# tinker.net
KiCad netlist of a schematic drawn in EAGLE
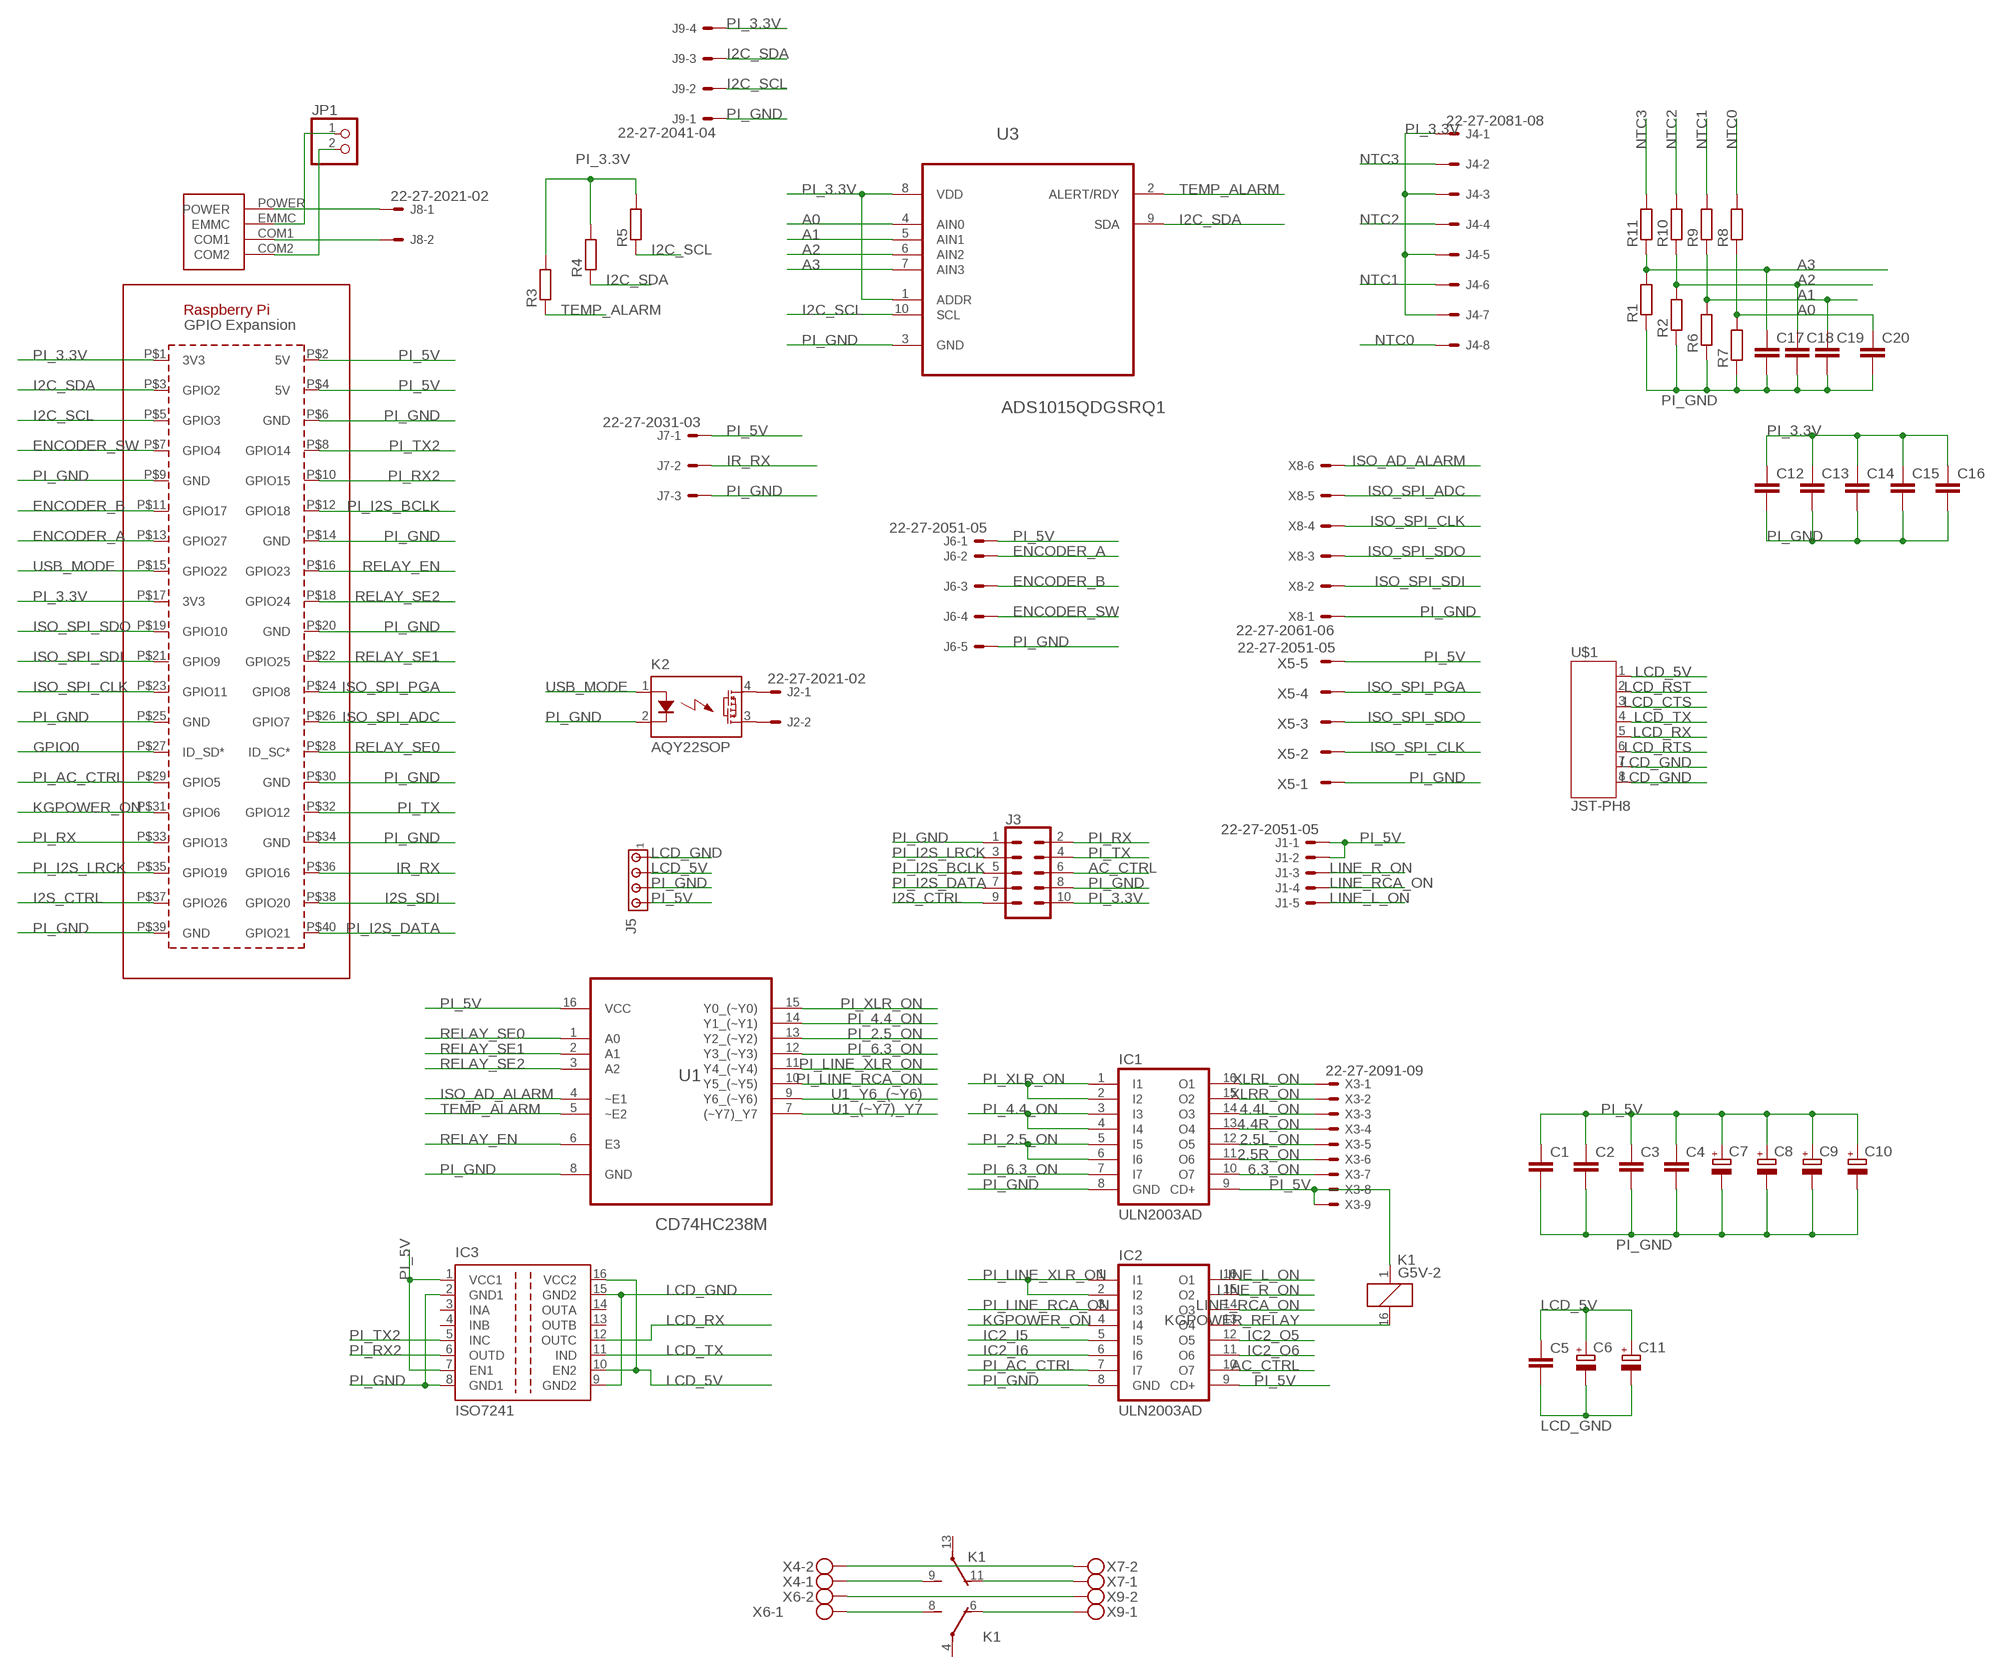
[diagram p0: schematic, sheet 1]

(export (version "E")
  (design (tool "Eeschema 10.0.6"))
  (components
    (comp (ref "C1")
      (value "C-EUC0603")
      (footprint "eagle-import:C0603")
      (libsource (lib "eagle-import") (part "C-EUC0603"))
    )
    (comp (ref "C2")
      (value "C-EUC0603")
      (footprint "eagle-import:C0603")
      (libsource (lib "eagle-import") (part "C-EUC0603"))
    )
    (comp (ref "C3")
      (value "C-EUC0603")
      (footprint "eagle-import:C0603")
      (libsource (lib "eagle-import") (part "C-EUC0603"))
    )
    (comp (ref "C4")
      (value "C-EUC0603")
      (footprint "eagle-import:C0603")
      (libsource (lib "eagle-import") (part "C-EUC0603"))
    )
    (comp (ref "C5")
      (value "C-EUC0603")
      (footprint "eagle-import:C0603")
      (libsource (lib "eagle-import") (part "C-EUC0603"))
    )
    (comp (ref "C6")
      (value "CPOL-EUSP-CAP-CX")
      (footprint "eagle-import:SP-CAP-CX")
      (libsource (lib "eagle-import") (part "CPOL-EUSP-CAP-CX"))
    )
    (comp (ref "C7")
      (value "CPOL-EUE5-10.5")
      (footprint "eagle-import:E5-10,5")
      (libsource (lib "eagle-import") (part "CPOL-EUE5-10.5"))
    )
    (comp (ref "C8")
      (value "CPOL-EUE5-10.5")
      (footprint "eagle-import:E5-10,5")
      (libsource (lib "eagle-import") (part "CPOL-EUE5-10.5"))
    )
    (comp (ref "C9")
      (value "CPOL-EUE5-10.5")
      (footprint "eagle-import:E5-10,5")
      (libsource (lib "eagle-import") (part "CPOL-EUE5-10.5"))
    )
    (comp (ref "C10")
      (value "CPOL-EUE5-10.5")
      (footprint "eagle-import:E5-10,5")
      (libsource (lib "eagle-import") (part "CPOL-EUE5-10.5"))
    )
    (comp (ref "C11")
      (value "CPOL-EUSP-CAP-CX")
      (footprint "eagle-import:SP-CAP-CX")
      (libsource (lib "eagle-import") (part "CPOL-EUSP-CAP-CX"))
    )
    (comp (ref "C12")
      (value "C-EUC0603")
      (footprint "eagle-import:C0603")
      (libsource (lib "eagle-import") (part "C-EUC0603"))
    )
    (comp (ref "C13")
      (value "C-EUC0603")
      (footprint "eagle-import:C0603")
      (libsource (lib "eagle-import") (part "C-EUC0603"))
    )
    (comp (ref "C14")
      (value "C-EUC0603")
      (footprint "eagle-import:C0603")
      (libsource (lib "eagle-import") (part "C-EUC0603"))
    )
    (comp (ref "C15")
      (value "C-EUC0603")
      (footprint "eagle-import:C0603")
      (libsource (lib "eagle-import") (part "C-EUC0603"))
    )
    (comp (ref "C16")
      (value "C-EUC0603")
      (footprint "eagle-import:C0603")
      (libsource (lib "eagle-import") (part "C-EUC0603"))
    )
    (comp (ref "C17")
      (value "C-EUC0603")
      (footprint "eagle-import:C0603")
      (libsource (lib "eagle-import") (part "C-EUC0603"))
    )
    (comp (ref "C18")
      (value "C-EUC0603")
      (footprint "eagle-import:C0603")
      (libsource (lib "eagle-import") (part "C-EUC0603"))
    )
    (comp (ref "C19")
      (value "C-EUC0603")
      (footprint "eagle-import:C0603")
      (libsource (lib "eagle-import") (part "C-EUC0603"))
    )
    (comp (ref "C20")
      (value "C-EUC0603")
      (footprint "eagle-import:C0603")
      (libsource (lib "eagle-import") (part "C-EUC0603"))
    )
    (comp (ref "IC1")
      (value "ULN2003AD")
      (footprint "eagle-import:SO16")
      (libsource (lib "eagle-import") (part "ULN2003AD"))
    )
    (comp (ref "IC2")
      (value "ULN2003AD")
      (footprint "eagle-import:SO16")
      (libsource (lib "eagle-import") (part "ULN2003AD"))
    )
    (comp (ref "IC3")
      (value "ISO7241")
      (footprint "eagle-import:SO-16DW")
      (fields (field (name "MPN") "ISO7241CDW"))
      (libsource (lib "eagle-import") (part "ISO7241"))
    )
    (comp (ref "J1")
      (value "22-27-2051-05")
      (footprint "eagle-import:6410-05")
      (fields (field (name "MF") "MOLEX"))
      (libsource (lib "eagle-import") (part "22-?-0527-2051"))
    )
    (comp (ref "J2")
      (value "22-27-2021-02")
      (footprint "eagle-import:6410-02")
      (fields (field (name "MF") "MOLEX"))
      (libsource (lib "eagle-import") (part "22-?-0227-2021"))
    )
    (comp (ref "J3")
      (value "CONN_05X2SHD_LOCK")
      (footprint "eagle-import:2X5-SHROUDED_LOCK")
      (libsource (lib "eagle-import") (part "CONN_05X2SHD_LOCK"))
    )
    (comp (ref "J4")
      (value "22-27-2081-08")
      (footprint "eagle-import:6410-08")
      (fields (field (name "MF") "MOLEX"))
      (libsource (lib "eagle-import") (part "22-?-0827-2081"))
    )
    (comp (ref "J5")
      (value "MTA04-156")
      (footprint "eagle-import:1X4MTA")
      (libsource (lib "eagle-import") (part "MTA04-156"))
    )
    (comp (ref "J6")
      (value "22-27-2051-05")
      (footprint "eagle-import:6410-05")
      (fields (field (name "MF") "MOLEX"))
      (libsource (lib "eagle-import") (part "22-?-0527-2051"))
    )
    (comp (ref "J7")
      (value "22-27-2031-03")
      (footprint "eagle-import:6410-03")
      (fields (field (name "MF") "MOLEX"))
      (libsource (lib "eagle-import") (part "22-?-0327-2031"))
    )
    (comp (ref "J8")
      (value "22-27-2021-02")
      (footprint "eagle-import:6410-02")
      (fields (field (name "MF") "MOLEX"))
      (libsource (lib "eagle-import") (part "22-?-0227-2021"))
    )
    (comp (ref "J9")
      (value "22-27-2041-04")
      (footprint "eagle-import:6410-04")
      (fields (field (name "MF") "MOLEX"))
      (libsource (lib "eagle-import") (part "22-?-0427-2041"))
    )
    (comp (ref "JP1")
      (value "PINHD-1X2")
      (footprint "eagle-import:1X02")
      (libsource (lib "eagle-import") (part "PINHD-1X2"))
    )
    (comp (ref "K1")
      (value "G5V-2")
      (footprint "eagle-import:G5V-2")
      (fields (field (name "MPN") "G5V-2 5DC"))
      (libsource (lib "eagle-import") (part "G5V-2"))
    )
    (comp (ref "K2")
      (value "AQY22SOP")
      (footprint "eagle-import:SOP04")
      (libsource (lib "eagle-import") (part "AQYSOP22"))
    )
    (comp (ref "PCB1")
      (value "RPI3")
      (footprint "eagle-import:RPI3")
      (libsource (lib "eagle-import") (part "RPI3"))
    )
    (comp (ref "R1")
      (value "R-EU_MELF0204W")
      (footprint "eagle-import:MINI_MELF-0204W")
      (libsource (lib "eagle-import") (part "R-EU_MELF0204W"))
    )
    (comp (ref "R2")
      (value "R-EU_MELF0204W")
      (footprint "eagle-import:MINI_MELF-0204W")
      (libsource (lib "eagle-import") (part "R-EU_MELF0204W"))
    )
    (comp (ref "R3")
      (value "R-EU_MELF0204W")
      (footprint "eagle-import:MINI_MELF-0204W")
      (libsource (lib "eagle-import") (part "R-EU_MELF0204W"))
    )
    (comp (ref "R4")
      (value "R-EU_MELF0204W")
      (footprint "eagle-import:MINI_MELF-0204W")
      (libsource (lib "eagle-import") (part "R-EU_MELF0204W"))
    )
    (comp (ref "R5")
      (value "R-EU_MELF0204W")
      (footprint "eagle-import:MINI_MELF-0204W")
      (libsource (lib "eagle-import") (part "R-EU_MELF0204W"))
    )
    (comp (ref "R6")
      (value "R-EU_MELF0204W")
      (footprint "eagle-import:MINI_MELF-0204W")
      (libsource (lib "eagle-import") (part "R-EU_MELF0204W"))
    )
    (comp (ref "R7")
      (value "R-EU_MELF0204W")
      (footprint "eagle-import:MINI_MELF-0204W")
      (libsource (lib "eagle-import") (part "R-EU_MELF0204W"))
    )
    (comp (ref "R8")
      (value "R-EU_MELF0204W")
      (footprint "eagle-import:MINI_MELF-0204W")
      (libsource (lib "eagle-import") (part "R-EU_MELF0204W"))
    )
    (comp (ref "R9")
      (value "R-EU_MELF0204W")
      (footprint "eagle-import:MINI_MELF-0204W")
      (libsource (lib "eagle-import") (part "R-EU_MELF0204W"))
    )
    (comp (ref "R10")
      (value "R-EU_MELF0204W")
      (footprint "eagle-import:MINI_MELF-0204W")
      (libsource (lib "eagle-import") (part "R-EU_MELF0204W"))
    )
    (comp (ref "R11")
      (value "R-EU_MELF0204W")
      (footprint "eagle-import:MINI_MELF-0204W")
      (libsource (lib "eagle-import") (part "R-EU_MELF0204W"))
    )
    (comp (ref "U$1")
      (value "JST-PH8")
      (footprint "eagle-import:JST-PH8")
      (libsource (lib "eagle-import") (part "JST-PH8"))
    )
    (comp (ref "U1")
      (value "CD74HC238M")
      (footprint "eagle-import:SOIC127P600X175-16N")
      (libsource (lib "eagle-import") (part "CD74HC238M"))
    )
    (comp (ref "U3")
      (value "ADS1015QDGSRQ1")
      (footprint "eagle-import:SOP50P490X110-10N")
      (libsource (lib "eagle-import") (part "ADS1015QDGSRQ1"))
    )
    (comp (ref "X3")
      (value "22-27-2091-09")
      (footprint "eagle-import:6410-09")
      (fields (field (name "MF") "MOLEX"))
      (libsource (lib "eagle-import") (part "22-?-0927-2091"))
    )
    (comp (ref "X4")
      (value "CON-PHOENIX-508_MKDSN1,5/2-5,08")
      (footprint "eagle-import:CON-PHOENIX-508_MKDSN1,5_2-5,08")
      (libsource (lib "eagle-import") (part "CON-PHOENIX-508_MKDSN1,5/2-5,08"))
    )
    (comp (ref "X5")
      (value "22-27-2051-05")
      (footprint "eagle-import:6410-05")
      (fields (field (name "MF") "MOLEX"))
      (libsource (lib "eagle-import") (part "22-?-0527-2051"))
    )
    (comp (ref "X6")
      (value "CON-PHOENIX-508_MKDSN1,5/2-5,08")
      (footprint "eagle-import:CON-PHOENIX-508_MKDSN1,5_2-5,08")
      (libsource (lib "eagle-import") (part "CON-PHOENIX-508_MKDSN1,5/2-5,08"))
    )
    (comp (ref "X7")
      (value "CON-PHOENIX-508_MKDSN1,5/2-5,08")
      (footprint "eagle-import:CON-PHOENIX-508_MKDSN1,5_2-5,08")
      (libsource (lib "eagle-import") (part "CON-PHOENIX-508_MKDSN1,5/2-5,08"))
    )
    (comp (ref "X8")
      (value "22-27-2061-06")
      (footprint "eagle-import:6410-06")
      (fields (field (name "MF") "MOLEX"))
      (libsource (lib "eagle-import") (part "22-?-0627-2061"))
    )
    (comp (ref "X9")
      (value "CON-PHOENIX-508_MKDSN1,5/2-5,08")
      (footprint "eagle-import:CON-PHOENIX-508_MKDSN1,5_2-5,08")
      (libsource (lib "eagle-import") (part "CON-PHOENIX-508_MKDSN1,5/2-5,08"))
    )
  )
  (nets
    (net (code "1") (name "/2.5L_ON") (class "Default")
      (node (ref "IC1") (pin "12") (pinfunction "O5_12") (pintype "open_collector"))
      (node (ref "X3") (pin "5") (pinfunction "S_5") (pintype "passive"))
    )
    (net (code "2") (name "/2.5R_ON") (class "Default")
      (node (ref "IC1") (pin "11") (pinfunction "O6_11") (pintype "open_collector"))
      (node (ref "X3") (pin "6") (pinfunction "S_6") (pintype "passive"))
    )
    (net (code "3") (name "/4.4L_ON") (class "Default")
      (node (ref "IC1") (pin "14") (pinfunction "O3_14") (pintype "open_collector"))
      (node (ref "X3") (pin "3") (pinfunction "S_3") (pintype "passive"))
    )
    (net (code "4") (name "/4.4R_ON") (class "Default")
      (node (ref "IC1") (pin "13") (pinfunction "O4_13") (pintype "open_collector"))
      (node (ref "X3") (pin "4") (pinfunction "S_4") (pintype "passive"))
    )
    (net (code "5") (name "/6.3_ON") (class "Default")
      (node (ref "IC1") (pin "10") (pinfunction "O7_10") (pintype "open_collector"))
      (node (ref "X3") (pin "7") (pinfunction "S_7") (pintype "passive"))
    )
    (net (code "6") (name "/A0") (class "Default")
      (node (ref "C20") (pin "1") (pinfunction "1_1") (pintype "passive"))
      (node (ref "R7") (pin "2") (pinfunction "2_2") (pintype "passive"))
      (node (ref "R8") (pin "1") (pinfunction "1_1") (pintype "passive"))
      (node (ref "U3") (pin "4") (pinfunction "AIN0_4") (pintype "input"))
    )
    (net (code "7") (name "/A1") (class "Default")
      (node (ref "C19") (pin "1") (pinfunction "1_1") (pintype "passive"))
      (node (ref "R6") (pin "2") (pinfunction "2_2") (pintype "passive"))
      (node (ref "R9") (pin "1") (pinfunction "1_1") (pintype "passive"))
      (node (ref "U3") (pin "5") (pinfunction "AIN1_5") (pintype "input"))
    )
    (net (code "8") (name "/A2") (class "Default")
      (node (ref "C18") (pin "1") (pinfunction "1_1") (pintype "passive"))
      (node (ref "R10") (pin "1") (pinfunction "1_1") (pintype "passive"))
      (node (ref "R2") (pin "2") (pinfunction "2_2") (pintype "passive"))
      (node (ref "U3") (pin "6") (pinfunction "AIN2_6") (pintype "input"))
    )
    (net (code "9") (name "/A3") (class "Default")
      (node (ref "C17") (pin "1") (pinfunction "1_1") (pintype "passive"))
      (node (ref "R1") (pin "2") (pinfunction "2_2") (pintype "passive"))
      (node (ref "R11") (pin "1") (pinfunction "1_1") (pintype "passive"))
      (node (ref "U3") (pin "7") (pinfunction "AIN3_7") (pintype "input"))
    )
    (net (code "10") (name "/AC_CTRL") (class "Default")
      (node (ref "IC2") (pin "10") (pinfunction "O7_10") (pintype "open_collector"))
      (node (ref "J3") (pin "6") (pinfunction "6_6") (pintype "passive"))
    )
    (net (code "11") (name "/ENCODER_A") (class "Default")
      (node (ref "J6") (pin "2") (pinfunction "S_2") (pintype "passive"))
      (node (ref "PCB1") (pin "P$13") (pinfunction "GPIO27_P$13") (pintype "bidirectional"))
    )
    (net (code "12") (name "/ENCODER_B") (class "Default")
      (node (ref "J6") (pin "3") (pinfunction "S_3") (pintype "passive"))
      (node (ref "PCB1") (pin "P$11") (pinfunction "GPIO17_P$11") (pintype "bidirectional"))
    )
    (net (code "13") (name "/ENCODER_SW") (class "Default")
      (node (ref "J6") (pin "4") (pinfunction "S_4") (pintype "passive"))
      (node (ref "PCB1") (pin "P$7") (pinfunction "GPIO4_P$7") (pintype "bidirectional"))
    )
    (net (code "14") (name "/GPIO0") (class "Default")
      (node (ref "PCB1") (pin "P$27") (pinfunction "ID_SD*_P$27") (pintype "bidirectional"))
    )
    (net (code "15") (name "/I2C_SCL") (class "Default")
      (node (ref "J9") (pin "2") (pinfunction "S_2") (pintype "passive"))
      (node (ref "PCB1") (pin "P$5") (pinfunction "GPIO3_P$5") (pintype "bidirectional"))
      (node (ref "R5") (pin "1") (pinfunction "1_1") (pintype "passive"))
      (node (ref "U3") (pin "10") (pinfunction "SCL_10") (pintype "input"))
    )
    (net (code "16") (name "/I2C_SDA") (class "Default")
      (node (ref "J9") (pin "3") (pinfunction "S_3") (pintype "passive"))
      (node (ref "PCB1") (pin "P$3") (pinfunction "GPIO2_P$3") (pintype "bidirectional"))
      (node (ref "R4") (pin "1") (pinfunction "1_1") (pintype "passive"))
      (node (ref "U3") (pin "9") (pinfunction "SDA_9") (pintype "bidirectional"))
    )
    (net (code "17") (name "/I2S_CTRL") (class "Default")
      (node (ref "J3") (pin "9") (pinfunction "9_9") (pintype "passive"))
      (node (ref "PCB1") (pin "P$37") (pinfunction "GPIO26_P$37") (pintype "bidirectional"))
    )
    (net (code "18") (name "/I2S_SDI") (class "Default")
      (node (ref "PCB1") (pin "P$38") (pinfunction "GPIO20_P$38") (pintype "bidirectional"))
    )
    (net (code "19") (name "/IC2_I5") (class "Default")
      (node (ref "IC2") (pin "5") (pinfunction "I5_5") (pintype "input"))
    )
    (net (code "20") (name "/IC2_I6") (class "Default")
      (node (ref "IC2") (pin "6") (pinfunction "I6_6") (pintype "input"))
    )
    (net (code "21") (name "/IC2_O5") (class "Default")
      (node (ref "IC2") (pin "12") (pinfunction "O5_12") (pintype "open_collector"))
    )
    (net (code "22") (name "/IC2_O6") (class "Default")
      (node (ref "IC2") (pin "11") (pinfunction "O6_11") (pintype "open_collector"))
    )
    (net (code "23") (name "/IR_RX") (class "Default")
      (node (ref "J7") (pin "2") (pinfunction "S_2") (pintype "passive"))
      (node (ref "PCB1") (pin "P$36") (pinfunction "GPIO16_P$36") (pintype "bidirectional"))
    )
    (net (code "24") (name "/ISO_AD_ALARM") (class "Default")
      (node (ref "U1") (pin "4") (pinfunction "~{E1}_4") (pintype "input"))
      (node (ref "X8") (pin "6") (pinfunction "S_6") (pintype "passive"))
    )
    (net (code "25") (name "/ISO_SPI_ADC") (class "Default")
      (node (ref "PCB1") (pin "P$26") (pinfunction "GPIO7_P$26") (pintype "bidirectional"))
      (node (ref "X8") (pin "5") (pinfunction "S_5") (pintype "passive"))
    )
    (net (code "26") (name "/ISO_SPI_CLK") (class "Default")
      (node (ref "PCB1") (pin "P$23") (pinfunction "GPIO11_P$23") (pintype "bidirectional"))
      (node (ref "X5") (pin "2") (pinfunction "S_2") (pintype "passive"))
      (node (ref "X8") (pin "4") (pinfunction "S_4") (pintype "passive"))
    )
    (net (code "27") (name "/ISO_SPI_PGA") (class "Default")
      (node (ref "PCB1") (pin "P$24") (pinfunction "GPIO8_P$24") (pintype "bidirectional"))
      (node (ref "X5") (pin "4") (pinfunction "S_4") (pintype "passive"))
    )
    (net (code "28") (name "/ISO_SPI_SDI") (class "Default")
      (node (ref "PCB1") (pin "P$21") (pinfunction "GPIO9_P$21") (pintype "bidirectional"))
      (node (ref "X8") (pin "2") (pinfunction "S_2") (pintype "passive"))
    )
    (net (code "29") (name "/ISO_SPI_SDO") (class "Default")
      (node (ref "PCB1") (pin "P$19") (pinfunction "GPIO10_P$19") (pintype "bidirectional"))
      (node (ref "X5") (pin "3") (pinfunction "S_3") (pintype "passive"))
      (node (ref "X8") (pin "3") (pinfunction "S_3") (pintype "passive"))
    )
    (net (code "30") (name "/KGPOWER_ON") (class "Default")
      (node (ref "IC2") (pin "4") (pinfunction "I4_4") (pintype "input"))
      (node (ref "PCB1") (pin "P$31") (pinfunction "GPIO6_P$31") (pintype "bidirectional"))
    )
    (net (code "31") (name "/KGPOWER_RELAY") (class "Default")
      (node (ref "IC2") (pin "13") (pinfunction "O4_13") (pintype "open_collector"))
      (node (ref "K1") (pin "16") (pinfunction "2_16") (pintype "passive"))
    )
    (net (code "32") (name "/LCD_5V") (class "Default")
      (node (ref "C11") (pin "+") (pinfunction "+_+") (pintype "passive"))
      (node (ref "C5") (pin "1") (pinfunction "1_1") (pintype "passive"))
      (node (ref "C6") (pin "+") (pinfunction "+_+") (pintype "passive"))
      (node (ref "IC3") (pin "10") (pinfunction "EN2_10") (pintype "input"))
      (node (ref "IC3") (pin "16") (pinfunction "VCC2_16") (pintype "power_in"))
      (node (ref "J5") (pin "2") (pinfunction "2_2") (pintype "passive"))
      (node (ref "U$1") (pin "1") (pinfunction "1_1") (pintype "passive"))
    )
    (net (code "33") (name "/LCD_CTS") (class "Default")
      (node (ref "U$1") (pin "3") (pinfunction "3_3") (pintype "passive"))
    )
    (net (code "34") (name "/LCD_GND") (class "Default")
      (node (ref "C11") (pin "-") (pinfunction "-_-") (pintype "passive"))
      (node (ref "C5") (pin "2") (pinfunction "2_2") (pintype "passive"))
      (node (ref "C6") (pin "-") (pinfunction "-_-") (pintype "passive"))
      (node (ref "IC3") (pin "15") (pinfunction "GND2_15") (pintype "power_in"))
      (node (ref "IC3") (pin "9") (pinfunction "GND2_9") (pintype "power_in"))
      (node (ref "J5") (pin "1") (pinfunction "1_1") (pintype "passive"))
      (node (ref "U$1") (pin "7") (pinfunction "7_7") (pintype "passive"))
      (node (ref "U$1") (pin "8") (pinfunction "8_8") (pintype "passive"))
    )
    (net (code "35") (name "/LCD_RST") (class "Default")
      (node (ref "U$1") (pin "2") (pinfunction "2_2") (pintype "passive"))
    )
    (net (code "36") (name "/LCD_RTS") (class "Default")
      (node (ref "U$1") (pin "6") (pinfunction "6_6") (pintype "passive"))
    )
    (net (code "37") (name "/LCD_RX") (class "Default")
      (node (ref "IC3") (pin "12") (pinfunction "OUTC_12") (pintype "output"))
      (node (ref "U$1") (pin "5") (pinfunction "5_5") (pintype "passive"))
    )
    (net (code "38") (name "/LCD_TX") (class "Default")
      (node (ref "IC3") (pin "11") (pinfunction "IND_11") (pintype "input"))
      (node (ref "U$1") (pin "4") (pinfunction "4_4") (pintype "passive"))
    )
    (net (code "39") (name "/LINE_L_ON") (class "Default")
      (node (ref "IC2") (pin "16") (pinfunction "O1_16") (pintype "open_collector"))
      (node (ref "J1") (pin "5") (pinfunction "S_5") (pintype "passive"))
    )
    (net (code "40") (name "/LINE_RCA_ON") (class "Default")
      (node (ref "IC2") (pin "14") (pinfunction "O3_14") (pintype "open_collector"))
      (node (ref "J1") (pin "4") (pinfunction "S_4") (pintype "passive"))
    )
    (net (code "41") (name "/LINE_R_ON") (class "Default")
      (node (ref "IC2") (pin "15") (pinfunction "O2_15") (pintype "open_collector"))
      (node (ref "J1") (pin "3") (pinfunction "S_3") (pintype "passive"))
    )
    (net (code "42") (name "/NTC0") (class "Default")
      (node (ref "J4") (pin "8") (pinfunction "S_8") (pintype "passive"))
      (node (ref "R8") (pin "2") (pinfunction "2_2") (pintype "passive"))
    )
    (net (code "43") (name "/NTC1") (class "Default")
      (node (ref "J4") (pin "6") (pinfunction "S_6") (pintype "passive"))
      (node (ref "R9") (pin "2") (pinfunction "2_2") (pintype "passive"))
    )
    (net (code "44") (name "/NTC2") (class "Default")
      (node (ref "J4") (pin "4") (pinfunction "S_4") (pintype "passive"))
      (node (ref "R10") (pin "2") (pinfunction "2_2") (pintype "passive"))
    )
    (net (code "45") (name "/NTC3") (class "Default")
      (node (ref "J4") (pin "2") (pinfunction "S_2") (pintype "passive"))
      (node (ref "R11") (pin "2") (pinfunction "2_2") (pintype "passive"))
    )
    (net (code "46") (name "/PI_2.5_ON") (class "Default")
      (node (ref "IC1") (pin "5") (pinfunction "I5_5") (pintype "input"))
      (node (ref "IC1") (pin "6") (pinfunction "I6_6") (pintype "input"))
      (node (ref "U1") (pin "13") (pinfunction "Y2_(~{Y2})_13") (pintype "output"))
    )
    (net (code "47") (name "/PI_3.3V") (class "Default")
      (node (ref "C12") (pin "1") (pinfunction "1_1") (pintype "passive"))
      (node (ref "C13") (pin "1") (pinfunction "1_1") (pintype "passive"))
      (node (ref "C14") (pin "1") (pinfunction "1_1") (pintype "passive"))
      (node (ref "C15") (pin "1") (pinfunction "1_1") (pintype "passive"))
      (node (ref "C16") (pin "1") (pinfunction "1_1") (pintype "passive"))
      (node (ref "J3") (pin "10") (pinfunction "10_10") (pintype "passive"))
      (node (ref "J4") (pin "1") (pinfunction "S_1") (pintype "passive"))
      (node (ref "J4") (pin "3") (pinfunction "S_3") (pintype "passive"))
      (node (ref "J4") (pin "5") (pinfunction "S_5") (pintype "passive"))
      (node (ref "J4") (pin "7") (pinfunction "S_7") (pintype "passive"))
      (node (ref "J9") (pin "4") (pinfunction "S_4") (pintype "passive"))
      (node (ref "PCB1") (pin "P$1") (pinfunction "3V3_P$1") (pintype "bidirectional"))
      (node (ref "PCB1") (pin "P$17") (pinfunction "3V3_P$17") (pintype "bidirectional"))
      (node (ref "R3") (pin "2") (pinfunction "2_2") (pintype "passive"))
      (node (ref "R4") (pin "2") (pinfunction "2_2") (pintype "passive"))
      (node (ref "R5") (pin "2") (pinfunction "2_2") (pintype "passive"))
      (node (ref "U3") (pin "1") (pinfunction "ADDR_1") (pintype "input"))
      (node (ref "U3") (pin "8") (pinfunction "VDD_8") (pintype "power_in"))
    )
    (net (code "48") (name "/PI_4.4_ON") (class "Default")
      (node (ref "IC1") (pin "3") (pinfunction "I3_3") (pintype "input"))
      (node (ref "IC1") (pin "4") (pinfunction "I4_4") (pintype "input"))
      (node (ref "U1") (pin "14") (pinfunction "Y1_(~{Y1})_14") (pintype "output"))
    )
    (net (code "49") (name "/PI_5V") (class "Default")
      (node (ref "C1") (pin "1") (pinfunction "1_1") (pintype "passive"))
      (node (ref "C10") (pin "+") (pinfunction "+_+") (pintype "passive"))
      (node (ref "C2") (pin "1") (pinfunction "1_1") (pintype "passive"))
      (node (ref "C3") (pin "1") (pinfunction "1_1") (pintype "passive"))
      (node (ref "C4") (pin "1") (pinfunction "1_1") (pintype "passive"))
      (node (ref "C7") (pin "+") (pinfunction "+_+") (pintype "passive"))
      (node (ref "C8") (pin "+") (pinfunction "+_+") (pintype "passive"))
      (node (ref "C9") (pin "+") (pinfunction "+_+") (pintype "passive"))
      (node (ref "IC1") (pin "9") (pinfunction "CD+_9") (pintype "passive"))
      (node (ref "IC2") (pin "9") (pinfunction "CD+_9") (pintype "passive"))
      (node (ref "IC3") (pin "1") (pinfunction "VCC1_1") (pintype "power_in"))
      (node (ref "IC3") (pin "7") (pinfunction "EN1_7") (pintype "input"))
      (node (ref "J1") (pin "1") (pinfunction "S_1") (pintype "passive"))
      (node (ref "J1") (pin "2") (pinfunction "S_2") (pintype "passive"))
      (node (ref "J5") (pin "4") (pinfunction "4_4") (pintype "passive"))
      (node (ref "J6") (pin "1") (pinfunction "S_1") (pintype "passive"))
      (node (ref "J7") (pin "1") (pinfunction "S_1") (pintype "passive"))
      (node (ref "K1") (pin "1") (pinfunction "1_1") (pintype "passive"))
      (node (ref "PCB1") (pin "P$2") (pinfunction "5V_P$2") (pintype "bidirectional"))
      (node (ref "PCB1") (pin "P$4") (pinfunction "5V_P$4") (pintype "bidirectional"))
      (node (ref "U1") (pin "16") (pinfunction "VCC_16") (pintype "input"))
      (node (ref "X3") (pin "8") (pinfunction "S_8") (pintype "passive"))
      (node (ref "X3") (pin "9") (pinfunction "S_9") (pintype "passive"))
      (node (ref "X5") (pin "5") (pinfunction "S_5") (pintype "passive"))
    )
    (net (code "50") (name "/PI_6.3_ON") (class "Default")
      (node (ref "IC1") (pin "7") (pinfunction "I7_7") (pintype "input"))
      (node (ref "U1") (pin "12") (pinfunction "Y3_(~{Y3})_12") (pintype "output"))
    )
    (net (code "51") (name "/PI_AC_CTRL") (class "Default")
      (node (ref "IC2") (pin "7") (pinfunction "I7_7") (pintype "input"))
      (node (ref "PCB1") (pin "P$29") (pinfunction "GPIO5_P$29") (pintype "bidirectional"))
    )
    (net (code "52") (name "/PI_GND") (class "Default")
      (node (ref "C1") (pin "2") (pinfunction "2_2") (pintype "passive"))
      (node (ref "C10") (pin "-") (pinfunction "-_-") (pintype "passive"))
      (node (ref "C12") (pin "2") (pinfunction "2_2") (pintype "passive"))
      (node (ref "C13") (pin "2") (pinfunction "2_2") (pintype "passive"))
      (node (ref "C14") (pin "2") (pinfunction "2_2") (pintype "passive"))
      (node (ref "C15") (pin "2") (pinfunction "2_2") (pintype "passive"))
      (node (ref "C16") (pin "2") (pinfunction "2_2") (pintype "passive"))
      (node (ref "C17") (pin "2") (pinfunction "2_2") (pintype "passive"))
      (node (ref "C18") (pin "2") (pinfunction "2_2") (pintype "passive"))
      (node (ref "C19") (pin "2") (pinfunction "2_2") (pintype "passive"))
      (node (ref "C2") (pin "2") (pinfunction "2_2") (pintype "passive"))
      (node (ref "C20") (pin "2") (pinfunction "2_2") (pintype "passive"))
      (node (ref "C3") (pin "2") (pinfunction "2_2") (pintype "passive"))
      (node (ref "C4") (pin "2") (pinfunction "2_2") (pintype "passive"))
      (node (ref "C7") (pin "-") (pinfunction "-_-") (pintype "passive"))
      (node (ref "C8") (pin "-") (pinfunction "-_-") (pintype "passive"))
      (node (ref "C9") (pin "-") (pinfunction "-_-") (pintype "passive"))
      (node (ref "IC1") (pin "8") (pinfunction "GND_8") (pintype "power_in"))
      (node (ref "IC2") (pin "8") (pinfunction "GND_8") (pintype "power_in"))
      (node (ref "IC3") (pin "2") (pinfunction "GND1_2") (pintype "power_in"))
      (node (ref "IC3") (pin "8") (pinfunction "GND1_8") (pintype "power_in"))
      (node (ref "J3") (pin "1") (pinfunction "1_1") (pintype "passive"))
      (node (ref "J3") (pin "8") (pinfunction "8_8") (pintype "passive"))
      (node (ref "J5") (pin "3") (pinfunction "3_3") (pintype "passive"))
      (node (ref "J6") (pin "5") (pinfunction "S_5") (pintype "passive"))
      (node (ref "J7") (pin "3") (pinfunction "S_3") (pintype "passive"))
      (node (ref "J9") (pin "1") (pinfunction "S_1") (pintype "passive"))
      (node (ref "K2") (pin "2") (pinfunction "K_2") (pintype "passive"))
      (node (ref "PCB1") (pin "P$14") (pinfunction "GND_P$14") (pintype "bidirectional"))
      (node (ref "PCB1") (pin "P$20") (pinfunction "GND_P$20") (pintype "bidirectional"))
      (node (ref "PCB1") (pin "P$25") (pinfunction "GND_P$25") (pintype "bidirectional"))
      (node (ref "PCB1") (pin "P$30") (pinfunction "GND_P$30") (pintype "bidirectional"))
      (node (ref "PCB1") (pin "P$34") (pinfunction "GND_P$34") (pintype "bidirectional"))
      (node (ref "PCB1") (pin "P$39") (pinfunction "GND_P$39") (pintype "bidirectional"))
      (node (ref "PCB1") (pin "P$6") (pinfunction "GND_P$6") (pintype "bidirectional"))
      (node (ref "PCB1") (pin "P$9") (pinfunction "GND_P$9") (pintype "bidirectional"))
      (node (ref "R1") (pin "1") (pinfunction "1_1") (pintype "passive"))
      (node (ref "R2") (pin "1") (pinfunction "1_1") (pintype "passive"))
      (node (ref "R6") (pin "1") (pinfunction "1_1") (pintype "passive"))
      (node (ref "R7") (pin "1") (pinfunction "1_1") (pintype "passive"))
      (node (ref "U1") (pin "8") (pinfunction "GND_8") (pintype "passive"))
      (node (ref "U3") (pin "3") (pinfunction "GND_3") (pintype "passive"))
      (node (ref "X5") (pin "1") (pinfunction "S_1") (pintype "passive"))
      (node (ref "X8") (pin "1") (pinfunction "S_1") (pintype "passive"))
    )
    (net (code "53") (name "/PI_I2S_BCLK") (class "Default")
      (node (ref "J3") (pin "5") (pinfunction "5_5") (pintype "passive"))
      (node (ref "PCB1") (pin "P$12") (pinfunction "GPIO18_P$12") (pintype "bidirectional"))
    )
    (net (code "54") (name "/PI_I2S_DATA") (class "Default")
      (node (ref "J3") (pin "7") (pinfunction "7_7") (pintype "passive"))
      (node (ref "PCB1") (pin "P$40") (pinfunction "GPIO21_P$40") (pintype "bidirectional"))
    )
    (net (code "55") (name "/PI_I2S_LRCK") (class "Default")
      (node (ref "J3") (pin "3") (pinfunction "3_3") (pintype "passive"))
      (node (ref "PCB1") (pin "P$35") (pinfunction "GPIO19_P$35") (pintype "bidirectional"))
    )
    (net (code "56") (name "/PI_LINE_RCA_ON") (class "Default")
      (node (ref "IC2") (pin "3") (pinfunction "I3_3") (pintype "input"))
      (node (ref "U1") (pin "10") (pinfunction "Y5_(~{Y5})_10") (pintype "output"))
    )
    (net (code "57") (name "/PI_LINE_XLR_ON") (class "Default")
      (node (ref "IC2") (pin "1") (pinfunction "I1_1") (pintype "input"))
      (node (ref "IC2") (pin "2") (pinfunction "I2_2") (pintype "input"))
      (node (ref "U1") (pin "11") (pinfunction "Y4_(~{Y4})_11") (pintype "output"))
    )
    (net (code "58") (name "/PI_RX") (class "Default")
      (node (ref "J3") (pin "2") (pinfunction "2_2") (pintype "passive"))
      (node (ref "PCB1") (pin "P$33") (pinfunction "GPIO13_P$33") (pintype "bidirectional"))
    )
    (net (code "59") (name "/PI_RX2") (class "Default")
      (node (ref "IC3") (pin "6") (pinfunction "OUTD_6") (pintype "output"))
      (node (ref "PCB1") (pin "P$10") (pinfunction "GPIO15_P$10") (pintype "bidirectional"))
    )
    (net (code "60") (name "/PI_TX") (class "Default")
      (node (ref "J3") (pin "4") (pinfunction "4_4") (pintype "passive"))
      (node (ref "PCB1") (pin "P$32") (pinfunction "GPIO12_P$32") (pintype "bidirectional"))
    )
    (net (code "61") (name "/PI_TX2") (class "Default")
      (node (ref "IC3") (pin "5") (pinfunction "INC_5") (pintype "input"))
      (node (ref "PCB1") (pin "P$8") (pinfunction "GPIO14_P$8") (pintype "bidirectional"))
    )
    (net (code "62") (name "/PI_XLR_ON") (class "Default")
      (node (ref "IC1") (pin "1") (pinfunction "I1_1") (pintype "input"))
      (node (ref "IC1") (pin "2") (pinfunction "I2_2") (pintype "input"))
      (node (ref "U1") (pin "15") (pinfunction "Y0_(~{Y0})_15") (pintype "output"))
    )
    (net (code "63") (name "/RELAY_EN") (class "Default")
      (node (ref "PCB1") (pin "P$16") (pinfunction "GPIO23_P$16") (pintype "bidirectional"))
      (node (ref "U1") (pin "6") (pinfunction "E3_6") (pintype "input"))
    )
    (net (code "64") (name "/RELAY_SE0") (class "Default")
      (node (ref "PCB1") (pin "P$28") (pinfunction "ID_SC*_P$28") (pintype "bidirectional"))
      (node (ref "U1") (pin "1") (pinfunction "A0_1") (pintype "input"))
    )
    (net (code "65") (name "/RELAY_SE1") (class "Default")
      (node (ref "PCB1") (pin "P$22") (pinfunction "GPIO25_P$22") (pintype "bidirectional"))
      (node (ref "U1") (pin "2") (pinfunction "A1_2") (pintype "input"))
    )
    (net (code "66") (name "/RELAY_SE2") (class "Default")
      (node (ref "PCB1") (pin "P$18") (pinfunction "GPIO24_P$18") (pintype "bidirectional"))
      (node (ref "U1") (pin "3") (pinfunction "A2_3") (pintype "input"))
    )
    (net (code "67") (name "/TEMP_ALARM") (class "Default")
      (node (ref "R3") (pin "1") (pinfunction "1_1") (pintype "passive"))
      (node (ref "U1") (pin "5") (pinfunction "~{E2}_5") (pintype "input"))
      (node (ref "U3") (pin "2") (pinfunction "ALERT/RDY_2") (pintype "output"))
    )
    (net (code "68") (name "/U1_(~{Y7})_Y7") (class "Default")
      (node (ref "U1") (pin "7") (pinfunction "(~{Y7})_Y7_7") (pintype "output"))
    )
    (net (code "69") (name "/U1_Y6_(~{Y6})") (class "Default")
      (node (ref "U1") (pin "9") (pinfunction "Y6_(~{Y6})_9") (pintype "output"))
    )
    (net (code "70") (name "/USB_MODE") (class "Default")
      (node (ref "K2") (pin "1") (pinfunction "A_1") (pintype "passive"))
      (node (ref "PCB1") (pin "P$15") (pinfunction "GPIO22_P$15") (pintype "bidirectional"))
    )
    (net (code "71") (name "/XLRL_ON") (class "Default")
      (node (ref "IC1") (pin "16") (pinfunction "O1_16") (pintype "open_collector"))
      (node (ref "X3") (pin "1") (pinfunction "S_1") (pintype "passive"))
    )
    (net (code "72") (name "/XLRR_ON") (class "Default")
      (node (ref "IC1") (pin "15") (pinfunction "O2_15") (pintype "open_collector"))
      (node (ref "X3") (pin "2") (pinfunction "S_2") (pintype "passive"))
    )
    (net (code "73") (name "Net-(J2A-S)") (class "Default")
      (node (ref "J2") (pin "1") (pinfunction "S_1") (pintype "passive"))
      (node (ref "K2") (pin "4") (pinfunction "DS1_4") (pintype "passive"))
    )
    (net (code "74") (name "Net-(J2B-S)") (class "Default")
      (node (ref "J2") (pin "2") (pinfunction "S_2") (pintype "passive"))
      (node (ref "K2") (pin "3") (pinfunction "DS2_3") (pintype "passive"))
    )
    (net (code "75") (name "Net-(J8A-S)") (class "Default")
      (node (ref "J8") (pin "1") (pinfunction "S_1") (pintype "passive"))
      (node (ref "PCB1") (pin "POWER") (pinfunction "POWER_POWER") (pintype "bidirectional"))
    )
    (net (code "76") (name "Net-(J8B-S)") (class "Default")
      (node (ref "J8") (pin "2") (pinfunction "S_2") (pintype "passive"))
      (node (ref "PCB1") (pin "COM1") (pinfunction "COM1_COM1") (pintype "bidirectional"))
    )
    (net (code "77") (name "Net-(JP1-Pad1)") (class "Default")
      (node (ref "JP1") (pin "1") (pinfunction "1_1") (pintype "passive"))
      (node (ref "PCB1") (pin "EMMC") (pinfunction "EMMC_EMMC") (pintype "bidirectional"))
    )
    (net (code "78") (name "Net-(JP1-Pad2)") (class "Default")
      (node (ref "JP1") (pin "2") (pinfunction "2_2") (pintype "passive"))
      (node (ref "PCB1") (pin "COM2") (pinfunction "COM2_COM2") (pintype "bidirectional"))
    )
    (net (code "79") (name "Net-(K1A-O)") (class "Default")
      (node (ref "K1") (pin "6") (pinfunction "O_6") (pintype "passive"))
      (node (ref "X9") (pin "1") (pinfunction "KL_1") (pintype "passive"))
    )
    (net (code "80") (name "Net-(K1A-S)") (class "Default")
      (node (ref "K1") (pin "8") (pinfunction "S_8") (pintype "passive"))
      (node (ref "X6") (pin "1") (pinfunction "KL_1") (pintype "passive"))
    )
    (net (code "81") (name "Net-(K1B-O)") (class "Default")
      (node (ref "K1") (pin "11") (pinfunction "O_11") (pintype "passive"))
      (node (ref "X7") (pin "1") (pinfunction "KL_1") (pintype "passive"))
    )
    (net (code "82") (name "Net-(K1B-S)") (class "Default")
      (node (ref "K1") (pin "9") (pinfunction "S_9") (pintype "passive"))
      (node (ref "X4") (pin "1") (pinfunction "KL_1") (pintype "passive"))
    )
    (net (code "83") (name "Net-(X4B-KL)") (class "Default")
      (node (ref "X4") (pin "2") (pinfunction "KL_2") (pintype "passive"))
      (node (ref "X7") (pin "2") (pinfunction "KL_2") (pintype "passive"))
    )
    (net (code "84") (name "Net-(X6B-KL)") (class "Default")
      (node (ref "X6") (pin "2") (pinfunction "KL_2") (pintype "passive"))
      (node (ref "X9") (pin "2") (pinfunction "KL_2") (pintype "passive"))
    )
    (net (code "85") (name "unconnected-(IC3-INA-Pad3)") (class "Default")
      (node (ref "IC3") (pin "3") (pinfunction "INA_3") (pintype "input"))
    )
    (net (code "86") (name "unconnected-(IC3-INB-Pad4)") (class "Default")
      (node (ref "IC3") (pin "4") (pinfunction "INB_4") (pintype "input"))
    )
    (net (code "87") (name "unconnected-(IC3-OUTA-Pad14)") (class "Default")
      (node (ref "IC3") (pin "14") (pinfunction "OUTA_14") (pintype "output"))
    )
    (net (code "88") (name "unconnected-(IC3-OUTB-Pad13)") (class "Default")
      (node (ref "IC3") (pin "13") (pinfunction "OUTB_13") (pintype "output"))
    )
    (net (code "89") (name "unconnected-(K1A-P-Pad4)") (class "Default")
      (node (ref "K1") (pin "4") (pinfunction "P_4") (pintype "passive"))
    )
    (net (code "90") (name "unconnected-(K1B-P-Pad13)") (class "Default")
      (node (ref "K1") (pin "13") (pinfunction "P_13") (pintype "passive"))
    )
  )
)
